# FX_Peripherals.net
KiCad netlist of a schematic drawn in Altium Designer
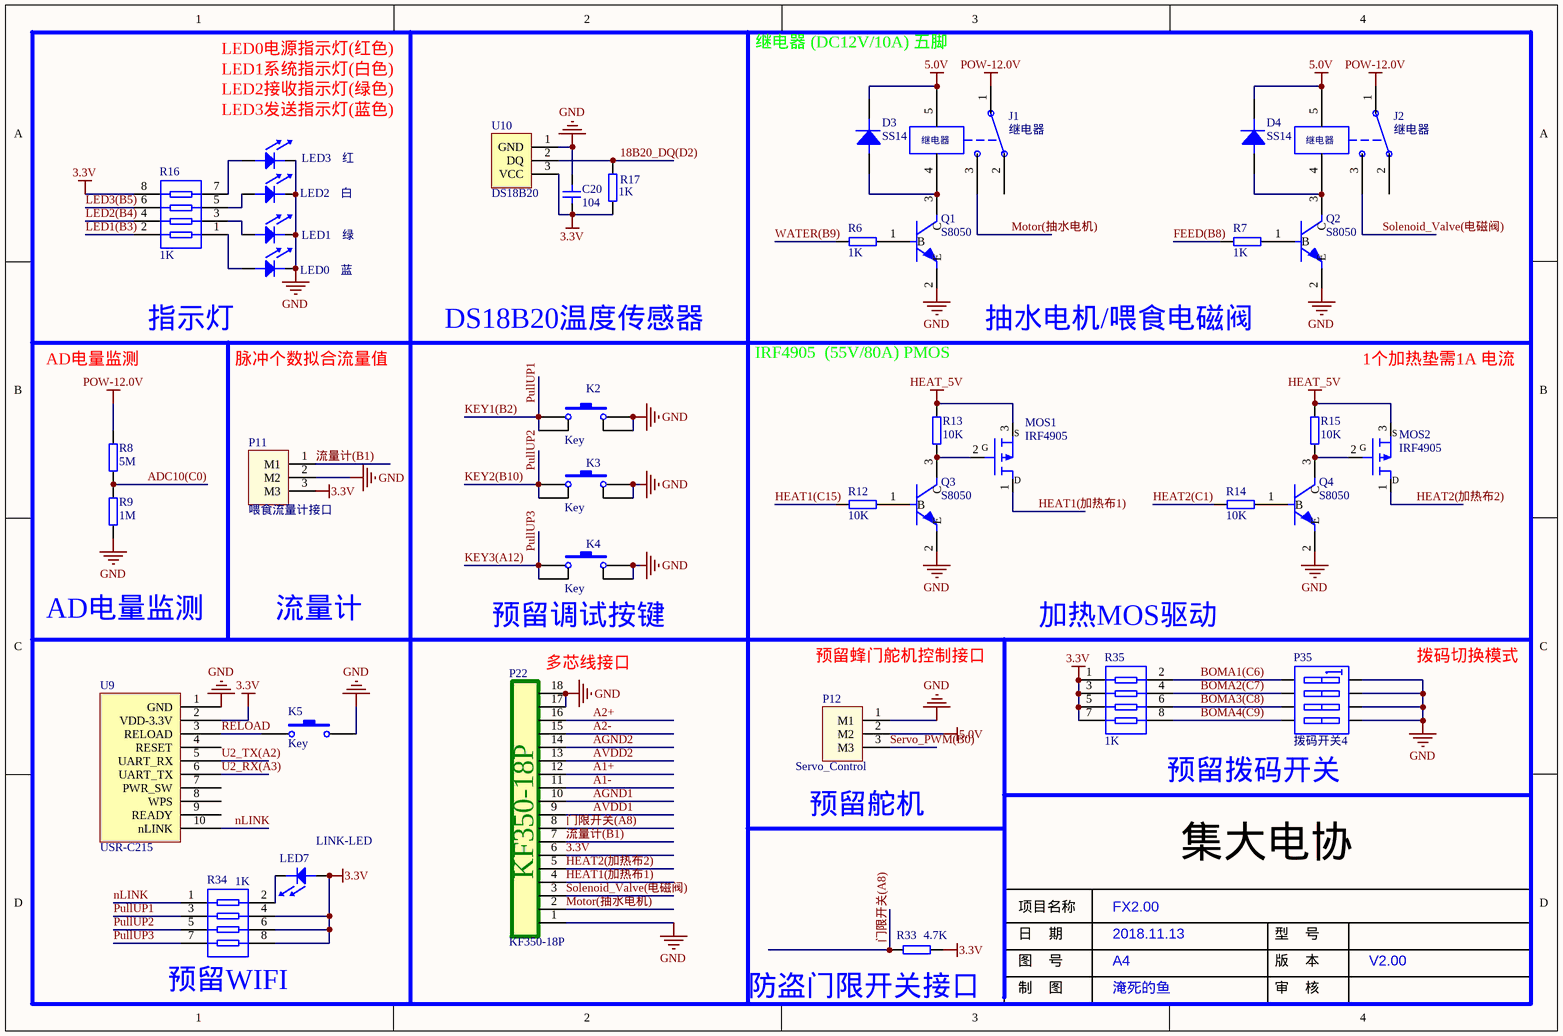
[diagram p0: FX_Peripherals.SchDoc]

(export (version "E")
  (design (tool "Eeschema 10.0.6"))
  (components
    (comp (ref "C20")
      (value "104")
      (footprint "0805C")
      (description "无极贴片电容")
      (libsource (lib "集大电协1.1.0") (part "Cap1"))
    )
    (comp (ref "D3")
      (value "SS14")
      (footprint "SMA/DO-214AC")
      (description "二极管")
      (libsource (lib "集大电协1.1.0") (part "Diode"))
    )
    (comp (ref "D4")
      (value "SS14")
      (footprint "SMA/DO-214AC")
      (description "二极管")
      (libsource (lib "集大电协1.1.0") (part "Diode"))
    )
    (comp (ref "J1") (value "继电器") (footprint "继电器(小型)") (libsource (lib "集大电协1.1.0") (part "继电器")))
    (comp (ref "J2") (value "继电器") (footprint "继电器(小型)") (libsource (lib "集大电协1.1.0") (part "继电器")))
    (comp (ref "K2")
      (value "Key")
      (footprint "SW_PB4_DIP")
      (description "四脚按键")
      (libsource (lib "集大电协1.1.0") (part "轻触开关"))
    )
    (comp (ref "K3")
      (value "Key")
      (footprint "SW_PB4_DIP")
      (description "四脚按键")
      (libsource (lib "集大电协1.1.0") (part "轻触开关"))
    )
    (comp (ref "K4")
      (value "Key")
      (footprint "SW_PB4_DIP")
      (description "四脚按键")
      (libsource (lib "集大电协1.1.0") (part "轻触开关"))
    )
    (comp (ref "K5")
      (value "Key")
      (footprint "贴片按键")
      (description "轻触开关")
      (libsource (lib "集大电协1.1.0") (part "贴片按键"))
    )
    (comp (ref "LED0")
      (value "蓝")
      (footprint "0805LED")
      (description "发光二极管")
      (libsource (lib "集大电协1.1.0") (part "LED"))
    )
    (comp (ref "LED1")
      (value "绿")
      (footprint "0805LED")
      (description "发光二极管")
      (libsource (lib "集大电协1.1.0") (part "LED"))
    )
    (comp (ref "LED2")
      (value "白")
      (footprint "0805LED")
      (description "发光二极管")
      (libsource (lib "集大电协1.1.0") (part "LED"))
    )
    (comp (ref "LED3")
      (value "红")
      (footprint "0805LED")
      (description "发光二极管")
      (libsource (lib "集大电协1.1.0") (part "LED"))
    )
    (comp (ref "LED7")
      (value "LINK-LED")
      (footprint "0805LED")
      (description "发光二极管")
      (libsource (lib "集大电协1.1.0") (part "LED"))
    )
    (comp (ref "MOS1")
      (value "IRF4905")
      (footprint "IRF4905(PMOS)")
      (description "PMOS")
      (libsource (lib "集大电协1.1.0") (part "PMOS"))
    )
    (comp (ref "MOS2")
      (value "IRF4905")
      (footprint "IRF4905(PMOS)")
      (description "PMOS")
      (libsource (lib "集大电协1.1.0") (part "PMOS"))
    )
    (comp (ref "P11")
      (value "喂食流量计接口")
      (footprint "接线端子(2.54mm)-3PIN")
      (description "3PIN")
      (libsource (lib "集大电协1.1.0") (part "接线端子-3PIN"))
    )
    (comp (ref "P12")
      (value "Servo_Control")
      (footprint "接线端子(2.54mm)-3PIN")
      (description "3PIN")
      (libsource (lib "集大电协1.1.0") (part "接线端子-3PIN"))
    )
    (comp (ref "P22")
      (value "KF350-18P")
      (footprint "KF350-18P")
      (libsource (lib "集大电协1.1.0") (part "接线端子KF350-18P"))
    )
    (comp (ref "P35")
      (value "拨码开关4")
      (footprint "拨码开关(4位直插)")
      (description "4位拨码开关")
      (libsource (lib "集大电协1.1.0") (part "拨码开关4"))
    )
    (comp (ref "Q1")
      (value "S8050")
      (footprint "SOT-23")
      (description "NPN三极管")
      (libsource (lib "集大电协1.1.0") (part "NPN"))
    )
    (comp (ref "Q2")
      (value "S8050")
      (footprint "SOT-23")
      (description "NPN三极管")
      (libsource (lib "集大电协1.1.0") (part "NPN"))
    )
    (comp (ref "Q3")
      (value "S8050")
      (footprint "SOT-23")
      (description "NPN三极管")
      (libsource (lib "集大电协1.1.0") (part "NPN"))
    )
    (comp (ref "Q4")
      (value "S8050")
      (footprint "SOT-23")
      (description "NPN三极管")
      (libsource (lib "集大电协1.1.0") (part "NPN"))
    )
    (comp (ref "R6")
      (value "1K")
      (footprint "0805R")
      (description "电阻")
      (libsource (lib "集大电协1.1.0") (part "Res"))
    )
    (comp (ref "R7")
      (value "1K")
      (footprint "0805R")
      (description "电阻")
      (libsource (lib "集大电协1.1.0") (part "Res"))
    )
    (comp (ref "R8")
      (value "5M")
      (footprint "0805R")
      (description "电阻")
      (libsource (lib "集大电协1.1.0") (part "Res"))
    )
    (comp (ref "R9")
      (value "1M")
      (footprint "0805R")
      (description "电阻")
      (libsource (lib "集大电协1.1.0") (part "Res"))
    )
    (comp (ref "R12")
      (value "10K")
      (footprint "0805R")
      (description "电阻")
      (libsource (lib "集大电协1.1.0") (part "Res"))
    )
    (comp (ref "R13")
      (value "10K")
      (footprint "0805R")
      (description "电阻")
      (libsource (lib "集大电协1.1.0") (part "Res"))
    )
    (comp (ref "R14")
      (value "10K")
      (footprint "0805R")
      (description "电阻")
      (libsource (lib "集大电协1.1.0") (part "Res"))
    )
    (comp (ref "R15")
      (value "10K")
      (footprint "0805R")
      (description "电阻")
      (libsource (lib "集大电协1.1.0") (part "Res"))
    )
    (comp (ref "R16")
      (value "1K")
      (footprint "排阻(4位贴片)")
      (description "排阻")
      (libsource (lib "集大电协1.1.0") (part "Res-4"))
    )
    (comp (ref "R17")
      (value "1K")
      (footprint "0805R")
      (description "电阻")
      (libsource (lib "集大电协1.1.0") (part "Res"))
    )
    (comp (ref "R33")
      (value "4.7K")
      (footprint "0805R")
      (description "电阻")
      (libsource (lib "集大电协1.1.0") (part "Res"))
    )
    (comp (ref "R34")
      (value "1K")
      (footprint "排阻(4位贴片)")
      (description "排阻")
      (libsource (lib "集大电协1.1.0") (part "Res-4"))
    )
    (comp (ref "R35")
      (value "1K")
      (footprint "排阻(4位贴片)")
      (description "排阻")
      (libsource (lib "集大电协1.1.0") (part "Res-4"))
    )
    (comp (ref "U9")
      (value "USR-C215")
      (footprint "USR-C215")
      (description "WIFI模块")
      (libsource (lib "集大电协1.1.0") (part "USR-C215"))
    )
    (comp (ref "U10")
      (value "DS18B20")
      (footprint "TO-92")
      (description "数字温度传感器")
      (libsource (lib "集大电协1.1.0") (part "DS18B20"))
    )
  )
  (nets
    (net (code "1") (name "/18B20_DQ(D2)") (class "Default")
      (node (ref "R17") (pin "2") (pinfunction "2_2") (pintype "passive"))
      (node (ref "U10") (pin "2") (pinfunction "DQ_2") (pintype "passive"))
    )
    (net (code "2") (name "/A1+") (class "Default")
      (node (ref "P22") (pin "12") (pinfunction "12_12") (pintype "passive"))
    )
    (net (code "3") (name "/A1-") (class "Default")
      (node (ref "P22") (pin "11") (pinfunction "11_11") (pintype "passive"))
    )
    (net (code "4") (name "/A2+") (class "Default")
      (node (ref "P22") (pin "16") (pinfunction "16_16") (pintype "passive"))
    )
    (net (code "5") (name "/A2-") (class "Default")
      (node (ref "P22") (pin "15") (pinfunction "15_15") (pintype "passive"))
    )
    (net (code "6") (name "/ADC10(C0)") (class "Default")
      (node (ref "R8") (pin "2") (pinfunction "2_2") (pintype "passive"))
      (node (ref "R9") (pin "1") (pinfunction "1_1") (pintype "passive"))
    )
    (net (code "7") (name "/AGND1") (class "Default")
      (node (ref "P22") (pin "10") (pinfunction "10_10") (pintype "passive"))
    )
    (net (code "8") (name "/AGND2") (class "Default")
      (node (ref "P22") (pin "14") (pinfunction "14_14") (pintype "passive"))
    )
    (net (code "9") (name "/AVDD1") (class "Default")
      (node (ref "P22") (pin "9") (pinfunction "9_9") (pintype "passive"))
    )
    (net (code "10") (name "/AVDD2") (class "Default")
      (node (ref "P22") (pin "13") (pinfunction "13_13") (pintype "passive"))
    )
    (net (code "11") (name "/BOMA1(C6)") (class "Default")
      (node (ref "P35") (pin "1") (pinfunction "A1_1") (pintype "passive"))
      (node (ref "R35") (pin "2") (pinfunction "2_2") (pintype "passive"))
    )
    (net (code "12") (name "/BOMA2(C7)") (class "Default")
      (node (ref "P35") (pin "2") (pinfunction "A2_2") (pintype "passive"))
      (node (ref "R35") (pin "4") (pinfunction "4_4") (pintype "passive"))
    )
    (net (code "13") (name "/BOMA3(C8)") (class "Default")
      (node (ref "P35") (pin "3") (pinfunction "A3_3") (pintype "passive"))
      (node (ref "R35") (pin "6") (pinfunction "6_6") (pintype "passive"))
    )
    (net (code "14") (name "/BOMA4(C9)") (class "Default")
      (node (ref "P35") (pin "4") (pinfunction "A4_4") (pintype "passive"))
      (node (ref "R35") (pin "8") (pinfunction "8_8") (pintype "passive"))
    )
    (net (code "15") (name "/FEED(B8)") (class "Default")
      (node (ref "R7") (pin "2") (pinfunction "2_2") (pintype "passive"))
    )
    (net (code "16") (name "/HEAT1(C15)") (class "Default")
      (node (ref "R12") (pin "2") (pinfunction "2_2") (pintype "passive"))
    )
    (net (code "17") (name "/HEAT1(加热布1)") (class "Default")
      (node (ref "MOS1") (pin "1") (pinfunction "D_1") (pintype "passive"))
      (node (ref "P22") (pin "4") (pinfunction "4_4") (pintype "passive"))
    )
    (net (code "18") (name "/HEAT2(C1)") (class "Default")
      (node (ref "R14") (pin "2") (pinfunction "2_2") (pintype "passive"))
    )
    (net (code "19") (name "/HEAT2(加热布2)") (class "Default")
      (node (ref "MOS2") (pin "1") (pinfunction "D_1") (pintype "passive"))
      (node (ref "P22") (pin "5") (pinfunction "5_5") (pintype "passive"))
    )
    (net (code "20") (name "/KEY1(B2)") (class "Default")
      (node (ref "K2") (pin "1") (pinfunction "1_1") (pintype "passive"))
      (node (ref "K2") (pin "4") (pinfunction "4_4") (pintype "passive"))
      (node (ref "R34") (pin "3") (pinfunction "3_3") (pintype "passive"))
    )
    (net (code "21") (name "/KEY2(B10)") (class "Default")
      (node (ref "K3") (pin "1") (pinfunction "1_1") (pintype "passive"))
      (node (ref "K3") (pin "4") (pinfunction "4_4") (pintype "passive"))
      (node (ref "R34") (pin "5") (pinfunction "5_5") (pintype "passive"))
    )
    (net (code "22") (name "/KEY3(A12)") (class "Default")
      (node (ref "K4") (pin "1") (pinfunction "1_1") (pintype "passive"))
      (node (ref "K4") (pin "4") (pinfunction "4_4") (pintype "passive"))
      (node (ref "R34") (pin "7") (pinfunction "7_7") (pintype "passive"))
    )
    (net (code "23") (name "/LED1(B3)") (class "Default")
      (node (ref "R16") (pin "2") (pinfunction "2_2") (pintype "passive"))
    )
    (net (code "24") (name "/LED2(B4)") (class "Default")
      (node (ref "R16") (pin "4") (pinfunction "4_4") (pintype "passive"))
    )
    (net (code "25") (name "/LED3(B5)") (class "Default")
      (node (ref "R16") (pin "6") (pinfunction "6_6") (pintype "passive"))
    )
    (net (code "26") (name "/Motor(抽水电机)") (class "Default")
      (node (ref "J1") (pin "3") (pinfunction "3_3") (pintype "passive"))
      (node (ref "P22") (pin "2") (pinfunction "2_2") (pintype "passive"))
    )
    (net (code "27") (name "/RELOAD") (class "Default")
      (node (ref "K5") (pin "1") (pinfunction "1_1") (pintype "passive"))
      (node (ref "U9") (pin "3") (pinfunction "RELOAD_3") (pintype "passive"))
    )
    (net (code "28") (name "/Servo_PWM(B0)") (class "Default")
      (node (ref "P12") (pin "3") (pinfunction "M3_3") (pintype "passive"))
    )
    (net (code "29") (name "/Solenoid_Valve(电磁阀)") (class "Default")
      (node (ref "J2") (pin "3") (pinfunction "3_3") (pintype "passive"))
      (node (ref "P22") (pin "3") (pinfunction "3_3") (pintype "passive"))
    )
    (net (code "30") (name "/U2_RX(A3)") (class "Default")
      (node (ref "U9") (pin "6") (pinfunction "UART_TX_6") (pintype "passive"))
    )
    (net (code "31") (name "/U2_TX(A2)") (class "Default")
      (node (ref "U9") (pin "5") (pinfunction "UART_RX_5") (pintype "passive"))
    )
    (net (code "32") (name "/WATER(B9)") (class "Default")
      (node (ref "R6") (pin "2") (pinfunction "2_2") (pintype "passive"))
    )
    (net (code "33") (name "/nLINK") (class "Default")
      (node (ref "R34") (pin "1") (pinfunction "1_1") (pintype "passive"))
      (node (ref "U9") (pin "10") (pinfunction "nLINK_10") (pintype "passive"))
    )
    (net (code "34") (name "/流量计(B1)") (class "Default")
      (node (ref "P11") (pin "1") (pinfunction "M1_1") (pintype "passive"))
      (node (ref "P22") (pin "7") (pinfunction "7_7") (pintype "passive"))
    )
    (net (code "35") (name "/门限开关(A8)") (class "Default")
      (node (ref "P22") (pin "8") (pinfunction "8_8") (pintype "passive"))
      (node (ref "R33") (pin "1") (pinfunction "1_1") (pintype "passive"))
    )
    (net (code "36") (name "3.3V") (class "Default")
      (node (ref "C20") (pin "2") (pinfunction "2_2") (pintype "passive"))
      (node (ref "LED7") (pin "1") (pintype "passive"))
      (node (ref "P11") (pin "3") (pinfunction "M3_3") (pintype "passive"))
      (node (ref "P22") (pin "6") (pinfunction "6_6") (pintype "passive"))
      (node (ref "R16") (pin "8") (pinfunction "8_8") (pintype "passive"))
      (node (ref "R17") (pin "1") (pinfunction "1_1") (pintype "passive"))
      (node (ref "R33") (pin "2") (pinfunction "2_2") (pintype "passive"))
      (node (ref "R34") (pin "4") (pinfunction "4_4") (pintype "passive"))
      (node (ref "R34") (pin "6") (pinfunction "6_6") (pintype "passive"))
      (node (ref "R34") (pin "8") (pinfunction "8_8") (pintype "passive"))
      (node (ref "R35") (pin "1") (pinfunction "1_1") (pintype "passive"))
      (node (ref "R35") (pin "3") (pinfunction "3_3") (pintype "passive"))
      (node (ref "R35") (pin "5") (pinfunction "5_5") (pintype "passive"))
      (node (ref "R35") (pin "7") (pinfunction "7_7") (pintype "passive"))
      (node (ref "U10") (pin "3") (pinfunction "VCC_3") (pintype "passive"))
      (node (ref "U9") (pin "2") (pinfunction "VDD-3.3V_2") (pintype "passive"))
    )
    (net (code "37") (name "5.0V") (class "Default")
      (node (ref "D3") (pin "2") (pinfunction "2_2") (pintype "passive"))
      (node (ref "D4") (pin "2") (pinfunction "2_2") (pintype "passive"))
      (node (ref "J1") (pin "5") (pinfunction "5_5") (pintype "passive"))
      (node (ref "J2") (pin "5") (pinfunction "5_5") (pintype "passive"))
      (node (ref "P12") (pin "2") (pinfunction "M2_2") (pintype "passive"))
    )
    (net (code "38") (name "GND") (class "Default")
      (node (ref "C20") (pin "1") (pinfunction "1_1") (pintype "passive"))
      (node (ref "K2") (pin "2") (pinfunction "2_2") (pintype "passive"))
      (node (ref "K2") (pin "3") (pinfunction "3_3") (pintype "passive"))
      (node (ref "K3") (pin "2") (pinfunction "2_2") (pintype "passive"))
      (node (ref "K3") (pin "3") (pinfunction "3_3") (pintype "passive"))
      (node (ref "K4") (pin "2") (pinfunction "2_2") (pintype "passive"))
      (node (ref "K4") (pin "3") (pinfunction "3_3") (pintype "passive"))
      (node (ref "K5") (pin "2") (pinfunction "2_2") (pintype "passive"))
      (node (ref "LED0") (pin "2") (pinfunction "2_2") (pintype "passive"))
      (node (ref "LED1") (pin "2") (pinfunction "2_2") (pintype "passive"))
      (node (ref "LED2") (pin "2") (pinfunction "2_2") (pintype "passive"))
      (node (ref "LED3") (pin "2") (pinfunction "2_2") (pintype "passive"))
      (node (ref "P11") (pin "2") (pinfunction "M2_2") (pintype "passive"))
      (node (ref "P12") (pin "1") (pinfunction "M1_1") (pintype "passive"))
      (node (ref "P22") (pin "1") (pinfunction "1_1") (pintype "passive"))
      (node (ref "P22") (pin "17") (pinfunction "17_17") (pintype "passive"))
      (node (ref "P22") (pin "18") (pinfunction "18_18") (pintype "passive"))
      (node (ref "P35") (pin "5") (pinfunction "B4_5") (pintype "passive"))
      (node (ref "P35") (pin "6") (pinfunction "B3_6") (pintype "passive"))
      (node (ref "P35") (pin "7") (pinfunction "B2_7") (pintype "passive"))
      (node (ref "P35") (pin "8") (pinfunction "B1_8") (pintype "passive"))
      (node (ref "Q1") (pin "2") (pinfunction "E_2") (pintype "passive"))
      (node (ref "Q2") (pin "2") (pinfunction "E_2") (pintype "passive"))
      (node (ref "Q3") (pin "2") (pinfunction "E_2") (pintype "passive"))
      (node (ref "Q4") (pin "2") (pinfunction "E_2") (pintype "passive"))
      (node (ref "R9") (pin "2") (pinfunction "2_2") (pintype "passive"))
      (node (ref "U10") (pin "1") (pinfunction "GND_1") (pintype "passive"))
      (node (ref "U9") (pin "1") (pinfunction "GND_1") (pintype "passive"))
    )
    (net (code "39") (name "HEAT_5V") (class "Default")
      (node (ref "MOS1") (pin "3") (pinfunction "S_3") (pintype "passive"))
      (node (ref "MOS2") (pin "3") (pinfunction "S_3") (pintype "passive"))
      (node (ref "R13") (pin "1") (pinfunction "1_1") (pintype "passive"))
      (node (ref "R15") (pin "1") (pinfunction "1_1") (pintype "passive"))
    )
    (net (code "40") (name "Net-(LED0-Pad1)") (class "Default")
      (node (ref "LED0") (pin "1") (pintype "passive"))
      (node (ref "R16") (pin "1") (pinfunction "1_1") (pintype "passive"))
    )
    (net (code "41") (name "Net-(LED1-Pad1)") (class "Default")
      (node (ref "LED1") (pin "1") (pintype "passive"))
      (node (ref "R16") (pin "3") (pinfunction "3_3") (pintype "passive"))
    )
    (net (code "42") (name "Net-(LED2-Pad1)") (class "Default")
      (node (ref "LED2") (pin "1") (pintype "passive"))
      (node (ref "R16") (pin "5") (pinfunction "5_5") (pintype "passive"))
    )
    (net (code "43") (name "Net-(LED3-Pad1)") (class "Default")
      (node (ref "LED3") (pin "1") (pintype "passive"))
      (node (ref "R16") (pin "7") (pinfunction "7_7") (pintype "passive"))
    )
    (net (code "44") (name "Net-(LED7-Pad2)") (class "Default")
      (node (ref "LED7") (pin "2") (pinfunction "2_2") (pintype "passive"))
      (node (ref "R34") (pin "2") (pinfunction "2_2") (pintype "passive"))
    )
    (net (code "45") (name "Net-(MOS1-G)") (class "Default")
      (node (ref "MOS1") (pin "2") (pinfunction "G_2") (pintype "passive"))
      (node (ref "Q3") (pin "3") (pinfunction "C_3") (pintype "passive"))
      (node (ref "R13") (pin "2") (pinfunction "2_2") (pintype "passive"))
    )
    (net (code "46") (name "Net-(MOS2-G)") (class "Default")
      (node (ref "MOS2") (pin "2") (pinfunction "G_2") (pintype "passive"))
      (node (ref "Q4") (pin "3") (pinfunction "C_3") (pintype "passive"))
      (node (ref "R15") (pin "2") (pinfunction "2_2") (pintype "passive"))
    )
    (net (code "47") (name "Net-(Q1-B)") (class "Default")
      (node (ref "Q1") (pin "1") (pinfunction "B_1") (pintype "passive"))
      (node (ref "R6") (pin "1") (pinfunction "1_1") (pintype "passive"))
    )
    (net (code "48") (name "Net-(Q1-C)") (class "Default")
      (node (ref "D3") (pin "1") (pintype "passive"))
      (node (ref "J1") (pin "4") (pinfunction "4_4") (pintype "passive"))
      (node (ref "Q1") (pin "3") (pinfunction "C_3") (pintype "passive"))
    )
    (net (code "49") (name "Net-(Q2-B)") (class "Default")
      (node (ref "Q2") (pin "1") (pinfunction "B_1") (pintype "passive"))
      (node (ref "R7") (pin "1") (pinfunction "1_1") (pintype "passive"))
    )
    (net (code "50") (name "Net-(Q2-C)") (class "Default")
      (node (ref "D4") (pin "1") (pintype "passive"))
      (node (ref "J2") (pin "4") (pinfunction "4_4") (pintype "passive"))
      (node (ref "Q2") (pin "3") (pinfunction "C_3") (pintype "passive"))
    )
    (net (code "51") (name "Net-(Q3-B)") (class "Default")
      (node (ref "Q3") (pin "1") (pinfunction "B_1") (pintype "passive"))
      (node (ref "R12") (pin "1") (pinfunction "1_1") (pintype "passive"))
    )
    (net (code "52") (name "Net-(Q4-B)") (class "Default")
      (node (ref "Q4") (pin "1") (pinfunction "B_1") (pintype "passive"))
      (node (ref "R14") (pin "1") (pinfunction "1_1") (pintype "passive"))
    )
    (net (code "53") (name "POW-12.0V") (class "Default")
      (node (ref "J1") (pin "1") (pinfunction "1_1") (pintype "passive"))
      (node (ref "J2") (pin "1") (pinfunction "1_1") (pintype "passive"))
      (node (ref "R8") (pin "1") (pinfunction "1_1") (pintype "passive"))
    )
    (net (code "54") (name "unconnected-(J1-Pad2)") (class "Default")
      (node (ref "J1") (pin "2") (pinfunction "2_2") (pintype "passive"))
    )
    (net (code "55") (name "unconnected-(J2-Pad2)") (class "Default")
      (node (ref "J2") (pin "2") (pinfunction "2_2") (pintype "passive"))
    )
    (net (code "56") (name "unconnected-(U9-PWR_SW-Pad7)") (class "Default")
      (node (ref "U9") (pin "7") (pinfunction "PWR_SW_7") (pintype "passive"))
    )
    (net (code "57") (name "unconnected-(U9-READY-Pad9)") (class "Default")
      (node (ref "U9") (pin "9") (pinfunction "READY_9") (pintype "passive"))
    )
    (net (code "58") (name "unconnected-(U9-RESET-Pad4)") (class "Default")
      (node (ref "U9") (pin "4") (pinfunction "RESET_4") (pintype "passive"))
    )
    (net (code "59") (name "unconnected-(U9-WPS-Pad8)") (class "Default")
      (node (ref "U9") (pin "8") (pinfunction "WPS_8") (pintype "passive"))
    )
  )
)
